# Schematic.net
KiCad netlist of a schematic drawn in EAGLE
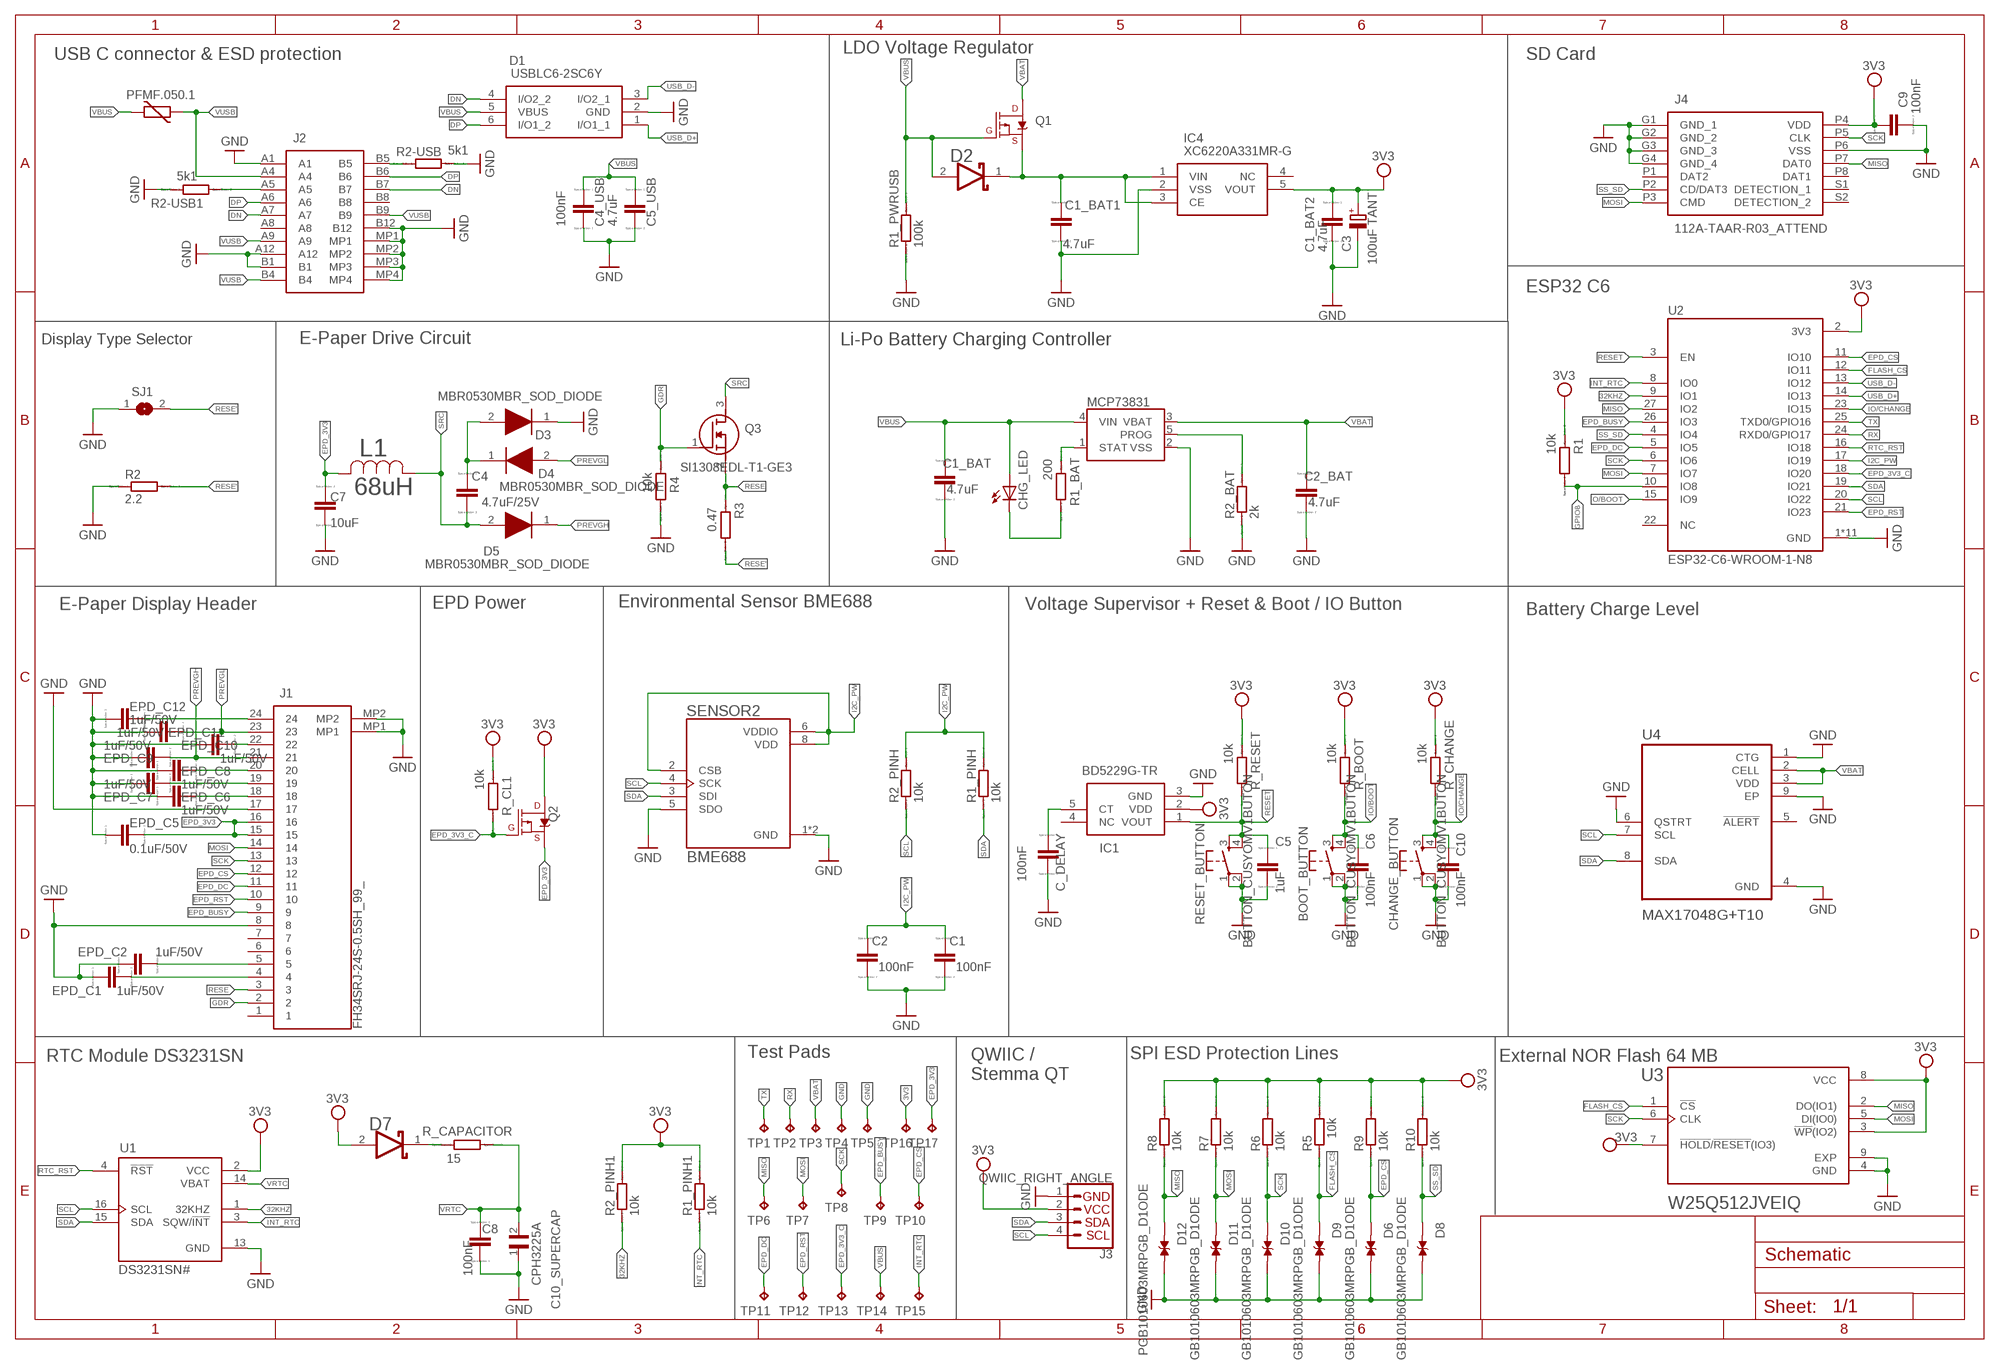
[diagram p0: schematic, sheet 1]

(export (version "E")
  (design (tool "Eeschema 10.0.6"))
  (components
    (comp (ref "BOOT_BUTTON")
      (value "BUTTON_CUSYOMV1BUTON")
      (footprint "eagle-import:MYBUTTON")
      (libsource (lib "eagle-import") (part "BUTTON_CUSYOMV1BUTON"))
    )
    (comp (ref "C1")
      (value "100nF")
      (footprint "eagle-import:ESP32_WROVER_EAGLE-LTSPICE_C0402")
      (libsource (lib "eagle-import") (part "ESP32_WROVER_EAGLE-LTSPICE_C"))
    )
    (comp (ref "C1_BAT")
      (value "4.7uF")
      (footprint "eagle-import:ESP32_WROVER_EAGLE-LTSPICE_C0402")
      (libsource (lib "eagle-import") (part "ESP32_WROVER_EAGLE-LTSPICE_C"))
    )
    (comp (ref "C1_BAT1")
      (value "4.7uF")
      (footprint "eagle-import:ESP32_WROVER_EAGLE-LTSPICE_C0402")
      (libsource (lib "eagle-import") (part "ESP32_WROVER_EAGLE-LTSPICE_C"))
    )
    (comp (ref "C1_BAT2")
      (value "4.7uF")
      (footprint "eagle-import:ESP32_WROVER_EAGLE-LTSPICE_C0402")
      (libsource (lib "eagle-import") (part "ESP32_WROVER_EAGLE-LTSPICE_C"))
    )
    (comp (ref "C2")
      (value "100nF")
      (footprint "eagle-import:ESP32_WROVER_EAGLE-LTSPICE_C0402")
      (libsource (lib "eagle-import") (part "ESP32_WROVER_EAGLE-LTSPICE_C"))
    )
    (comp (ref "C2_BAT")
      (value "4.7uF")
      (footprint "eagle-import:ESP32_WROVER_EAGLE-LTSPICE_C0402")
      (libsource (lib "eagle-import") (part "ESP32_WROVER_EAGLE-LTSPICE_C"))
    )
    (comp (ref "C3")
      (value "100uF TANT")
      (footprint "eagle-import:RCL_CT3528")
      (libsource (lib "eagle-import") (part "RCL_CPOL-EUCT3528"))
    )
    (comp (ref "C4")
      (value "4.7uF/25V")
      (footprint "eagle-import:ESP32_WROVER_EAGLE-LTSPICE_C0402")
      (libsource (lib "eagle-import") (part "ESP32_WROVER_EAGLE-LTSPICE_C"))
    )
    (comp (ref "C4_USB")
      (value "100nF")
      (footprint "eagle-import:ESP32_WROVER_EAGLE-LTSPICE_C0402")
      (libsource (lib "eagle-import") (part "ESP32_WROVER_EAGLE-LTSPICE_C"))
    )
    (comp (ref "C5")
      (value "1uF")
      (footprint "eagle-import:ESP32_WROVER_EAGLE-LTSPICE_C0402")
      (libsource (lib "eagle-import") (part "ESP32_WROVER_EAGLE-LTSPICE_C"))
    )
    (comp (ref "C5_USB")
      (value "4.7uF")
      (footprint "eagle-import:ESP32_WROVER_EAGLE-LTSPICE_C0402")
      (libsource (lib "eagle-import") (part "ESP32_WROVER_EAGLE-LTSPICE_C"))
    )
    (comp (ref "C6")
      (value "100nF")
      (footprint "eagle-import:ESP32_WROVER_EAGLE-LTSPICE_C0402")
      (libsource (lib "eagle-import") (part "ESP32_WROVER_EAGLE-LTSPICE_C"))
    )
    (comp (ref "C7")
      (value "10uF")
      (footprint "eagle-import:ESP32_WROVER_EAGLE-LTSPICE_C0402")
      (libsource (lib "eagle-import") (part "ESP32_WROVER_EAGLE-LTSPICE_C"))
    )
    (comp (ref "C8")
      (value "100nF")
      (footprint "eagle-import:ESP32_WROVER_EAGLE-LTSPICE_C0402")
      (libsource (lib "eagle-import") (part "ESP32_WROVER_EAGLE-LTSPICE_C"))
    )
    (comp (ref "C9")
      (value "100nF")
      (footprint "eagle-import:ESP32_WROVER_EAGLE-LTSPICE_C0402")
      (libsource (lib "eagle-import") (part "ESP32_WROVER_EAGLE-LTSPICE_C"))
    )
    (comp (ref "C10")
      (value "100nF")
      (footprint "eagle-import:ESP32_WROVER_EAGLE-LTSPICE_C0402")
      (libsource (lib "eagle-import") (part "ESP32_WROVER_EAGLE-LTSPICE_C"))
    )
    (comp (ref "C10_SUPERCAP")
      (value "CPH3225A")
      (footprint "eagle-import:CAPCP3225X100N")
      (fields (field (name "MF") "Seiko Instruments"))
      (libsource (lib "eagle-import") (part "CPH3225A"))
    )
    (comp (ref "CHANGE_BUTTON")
      (value "BUTTON_CUSYOMV1BUTON")
      (footprint "eagle-import:MYBUTTON")
      (libsource (lib "eagle-import") (part "BUTTON_CUSYOMV1BUTON"))
    )
    (comp (ref "CHG_LED")
      (value "ADAFRUIT_LEDCHIP-LED0603")
      (footprint "eagle-import:ADAFRUIT_CHIP-LED0603")
      (libsource (lib "eagle-import") (part "ADAFRUIT_LEDCHIP-LED0603"))
    )
    (comp (ref "C_DELAY")
      (value "100nF")
      (footprint "eagle-import:ESP32_WROVER_EAGLE-LTSPICE_C0402")
      (libsource (lib "eagle-import") (part "ESP32_WROVER_EAGLE-LTSPICE_C"))
    )
    (comp (ref "D1")
      (value "USBLC6-2SC6Y")
      (footprint "eagle-import:SOT95P280X145-6N")
      (fields (field (name "MF") "STMicroelectronics"))
      (libsource (lib "eagle-import") (part "USBLC6-2SC6Y"))
    )
    (comp (ref "D2")
      (value "ESP32_WROVER_AVX---SD0805S020S1R0_AVX_SD0805S020S1R0_0_0B1G_DIODE")
      (footprint "eagle-import:ESP32_WROVER_AVX---SD0805S020S1R0_AVX_SD0805S020S1R0_0")
      (libsource (lib "eagle-import") (part "ESP32_WROVER_AVX---SD0805S020S1R0_AVX_SD0805S020S1R0_0_0B1G_DIODE"))
    )
    (comp (ref "D3")
      (value "MBR0530MBR_SOD_DIODE")
      (footprint "eagle-import:SOD3716X135N")
      (libsource (lib "eagle-import") (part "MBR0530MBR_SOD_DIODE"))
    )
    (comp (ref "D4")
      (value "MBR0530MBR_SOD_DIODE")
      (footprint "eagle-import:SOD3716X135N")
      (libsource (lib "eagle-import") (part "MBR0530MBR_SOD_DIODE"))
    )
    (comp (ref "D5")
      (value "MBR0530MBR_SOD_DIODE")
      (footprint "eagle-import:SOD3716X135N")
      (libsource (lib "eagle-import") (part "MBR0530MBR_SOD_DIODE"))
    )
    (comp (ref "D6")
      (value "PGB1010603MRPGB_D1ODE")
      (footprint "eagle-import:DIOC1608X36N")
      (libsource (lib "eagle-import") (part "PGB1010603MRPGB_D1ODE"))
    )
    (comp (ref "D7")
      (value "ESP32_WROVER_AVX---SD0805S020S1R0_AVX_SD0805S020S1R0_0_0B1G_DIODE")
      (footprint "eagle-import:ESP32_WROVER_AVX---SD0805S020S1R0_AVX_SD0805S020S1R0_0")
      (libsource (lib "eagle-import") (part "ESP32_WROVER_AVX---SD0805S020S1R0_AVX_SD0805S020S1R0_0_0B1G_DIODE"))
    )
    (comp (ref "D8")
      (value "PGB1010603MRPGB_D1ODE")
      (footprint "eagle-import:DIOC1608X36N")
      (libsource (lib "eagle-import") (part "PGB1010603MRPGB_D1ODE"))
    )
    (comp (ref "D9")
      (value "PGB1010603MRPGB_D1ODE")
      (footprint "eagle-import:DIOC1608X36N")
      (libsource (lib "eagle-import") (part "PGB1010603MRPGB_D1ODE"))
    )
    (comp (ref "D10")
      (value "PGB1010603MRPGB_D1ODE")
      (footprint "eagle-import:DIOC1608X36N")
      (libsource (lib "eagle-import") (part "PGB1010603MRPGB_D1ODE"))
    )
    (comp (ref "D11")
      (value "PGB1010603MRPGB_D1ODE")
      (footprint "eagle-import:DIOC1608X36N")
      (libsource (lib "eagle-import") (part "PGB1010603MRPGB_D1ODE"))
    )
    (comp (ref "D12")
      (value "PGB1010603MRPGB_D1ODE")
      (footprint "eagle-import:DIOC1608X36N")
      (libsource (lib "eagle-import") (part "PGB1010603MRPGB_D1ODE"))
    )
    (comp (ref "EPD_C1")
      (value "1uF/50V")
      (footprint "eagle-import:ESP32_WROVER_EAGLE-LTSPICE_C0402")
      (libsource (lib "eagle-import") (part "ESP32_WROVER_EAGLE-LTSPICE_C"))
    )
    (comp (ref "EPD_C2")
      (value "1uF/50V")
      (footprint "eagle-import:ESP32_WROVER_EAGLE-LTSPICE_C0402")
      (libsource (lib "eagle-import") (part "ESP32_WROVER_EAGLE-LTSPICE_C"))
    )
    (comp (ref "EPD_C5")
      (value "0.1uF/50V")
      (footprint "eagle-import:ESP32_WROVER_EAGLE-LTSPICE_C0402")
      (libsource (lib "eagle-import") (part "ESP32_WROVER_EAGLE-LTSPICE_C"))
    )
    (comp (ref "EPD_C6")
      (value "1uF/50V")
      (footprint "eagle-import:ESP32_WROVER_EAGLE-LTSPICE_C0402")
      (libsource (lib "eagle-import") (part "ESP32_WROVER_EAGLE-LTSPICE_C"))
    )
    (comp (ref "EPD_C7")
      (value "1uF/50V")
      (footprint "eagle-import:ESP32_WROVER_EAGLE-LTSPICE_C0402")
      (libsource (lib "eagle-import") (part "ESP32_WROVER_EAGLE-LTSPICE_C"))
    )
    (comp (ref "EPD_C8")
      (value "1uF/50V")
      (footprint "eagle-import:ESP32_WROVER_EAGLE-LTSPICE_C0402")
      (libsource (lib "eagle-import") (part "ESP32_WROVER_EAGLE-LTSPICE_C"))
    )
    (comp (ref "EPD_C9")
      (value "1uF/50V")
      (footprint "eagle-import:ESP32_WROVER_EAGLE-LTSPICE_C0402")
      (libsource (lib "eagle-import") (part "ESP32_WROVER_EAGLE-LTSPICE_C"))
    )
    (comp (ref "EPD_C10")
      (value "1uF/50V")
      (footprint "eagle-import:ESP32_WROVER_EAGLE-LTSPICE_C0402")
      (libsource (lib "eagle-import") (part "ESP32_WROVER_EAGLE-LTSPICE_C"))
    )
    (comp (ref "EPD_C11")
      (value "1uF/50V")
      (footprint "eagle-import:ESP32_WROVER_EAGLE-LTSPICE_C0402")
      (libsource (lib "eagle-import") (part "ESP32_WROVER_EAGLE-LTSPICE_C"))
    )
    (comp (ref "EPD_C12")
      (value "1uF/50V")
      (footprint "eagle-import:ESP32_WROVER_EAGLE-LTSPICE_C0402")
      (libsource (lib "eagle-import") (part "ESP32_WROVER_EAGLE-LTSPICE_C"))
    )
    (comp (ref "IC1")
      (value "BD5229G-TR")
      (footprint "eagle-import:SOT95P280X125-5N")
      (fields (field (name "MOUSER_PART_NUMBER") "755-BD5229G-TR"))
      (libsource (lib "eagle-import") (part "BD5229G-TR"))
    )
    (comp (ref "IC4")
      (value "XC6220A331MR-G")
      (footprint "eagle-import:SOT95P280X120-5N")
      (fields (field (name "MOUSER_PART_NUMBER") "865-XC6220A331MR-G"))
      (libsource (lib "eagle-import") (part "XC6220A331MR-G"))
    )
    (comp (ref "J1")
      (value "FH34SRJ-24S-0.5SH_99_")
      (footprint "eagle-import:FH34SRJ24S05SH99")
      (fields
        (field (name "MANUFACTURER_PART_NUMBER") "FH34SRJ-24S-0.5SH(99)")
        (field (name "MOUSER_PART_NUMBER") "798-FH34SRJ24S05SH99")
      )
      (libsource (lib "eagle-import") (part "FH34SRJ-24S-0.5SH_99_"))
    )
    (comp (ref "J2")
      (value "SAMACSYS_PARTS_USB4110-GF-A")
      (footprint "eagle-import:SAMACSYS_PARTS_USB4110GFA")
      (fields
        (field (name "MANUFACTURER_PART_NUMBER") "USB4110-GF-A")
        (field (name "MOUSER_PART_NUMBER") "640-USB4110-GF-A")
      )
      (libsource (lib "eagle-import") (part "SAMACSYS_PARTS_USB4110-GF-A"))
    )
    (comp (ref "J3")
      (value "QWIIC_RIGHT_ANGLE")
      (footprint "eagle-import:JST04_1MM_RA")
      (libsource (lib "eagle-import") (part "QWIIC_CONNECTORJS-1MM"))
    )
    (comp (ref "J4")
      (value "112A-TAAR-R03_ATTEND")
      (footprint "eagle-import:112ATAARR03ATTEND")
      (fields (field (name "MANUFACTURER_PART_NUMBER") "112A-TAAR-R03 ATTEND"))
      (libsource (lib "eagle-import") (part "112A-TAAR-R03_ATTEND"))
    )
    (comp (ref "L1")
      (value "68uH")
      (footprint "eagle-import:IND_4828-WE-TPC_WRE")
      (fields
        (field (name "MANUFACTURER_PART_NUMBER") "744043680")
        (field (name "COPYRIGHT") "Copyright (C) 2024 Ultra Librarian. All rights reserved.")
      )
      (libsource (lib "eagle-import") (part "744043680IND_4828-WE-TPC_WRE"))
    )
    (comp (ref "MCP73831")
      (value "ESP32_WROVER_SPARKFUN-IC-POWER_MCP73831")
      (footprint "eagle-import:ESP32_WROVER_SPARKFUN-IC-POWER_SOT23-5")
      (libsource (lib "eagle-import") (part "ESP32_WROVER_SPARKFUN-IC-POWER_MCP73831"))
    )
    (comp (ref "PFMF.050.1")
      (value "ESP32C6_VARISTORPFMF_ESP32C6_VARISTORS")
      (footprint "eagle-import:ESP32C6_VARISTOR_CT_CN1812")
      (libsource (lib "eagle-import") (part "ESP32C6_VARISTORPFMF_ESP32C6_VARISTORS"))
    )
    (comp (ref "Q1")
      (value "20V/4.2A/52mΩ/1.4W")
      (footprint "eagle-import:ESP32_WROVER_SPARKFUN-DISCRETESEMI_SOT23-3")
      (libsource (lib "eagle-import") (part "ESP32_WROVER_SPARKFUN-DISCRETESEMI_MOSFET_PCH"))
    )
    (comp (ref "Q2")
      (value "20V/4.2A/52mΩ/1.4W")
      (footprint "eagle-import:ESP32_WROVER_SPARKFUN-DISCRETESEMI_SOT23-3")
      (libsource (lib "eagle-import") (part "ESP32_WROVER_SPARKFUN-DISCRETESEMI_MOSFET_PCH"))
    )
    (comp (ref "Q3")
      (value "SI1308EDL-T1-GE3")
      (footprint "eagle-import:SOT65P210X110-3N")
      (fields (field (name "MF") "Vishay Siliconix"))
      (libsource (lib "eagle-import") (part "SI1308EDL-T1-GE3"))
    )
    (comp (ref "R1")
      (value "10k")
      (footprint "eagle-import:ESP32_WROVER_EAGLE-LTSPICE_R0402")
      (libsource (lib "eagle-import") (part "ESP32_WROVER_EAGLE-LTSPICE_R"))
    )
    (comp (ref "R1_BAT")
      (value "200")
      (footprint "eagle-import:ESP32_WROVER_EAGLE-LTSPICE_R0402")
      (libsource (lib "eagle-import") (part "ESP32_WROVER_EAGLE-LTSPICE_R"))
    )
    (comp (ref "R1_PINH")
      (value "10k")
      (footprint "eagle-import:ESP32_WROVER_EAGLE-LTSPICE_R0402")
      (libsource (lib "eagle-import") (part "ESP32_WROVER_EAGLE-LTSPICE_R"))
    )
    (comp (ref "R1_PINH1")
      (value "10k")
      (footprint "eagle-import:ESP32_WROVER_EAGLE-LTSPICE_R0402")
      (libsource (lib "eagle-import") (part "ESP32_WROVER_EAGLE-LTSPICE_R"))
    )
    (comp (ref "R1_PWRUSB")
      (value "100k")
      (footprint "eagle-import:ESP32_WROVER_EAGLE-LTSPICE_R0402")
      (libsource (lib "eagle-import") (part "ESP32_WROVER_EAGLE-LTSPICE_R"))
    )
    (comp (ref "R2")
      (value "2.2")
      (footprint "eagle-import:ESP32_WROVER_EAGLE-LTSPICE_R0402")
      (libsource (lib "eagle-import") (part "ESP32_WROVER_EAGLE-LTSPICE_R"))
    )
    (comp (ref "R2-USB")
      (value "5k1")
      (footprint "eagle-import:ESP32_WROVER_EAGLE-LTSPICE_R0402")
      (libsource (lib "eagle-import") (part "ESP32_WROVER_EAGLE-LTSPICE_R"))
    )
    (comp (ref "R2-USB1")
      (value "5k1")
      (footprint "eagle-import:ESP32_WROVER_EAGLE-LTSPICE_R0402")
      (libsource (lib "eagle-import") (part "ESP32_WROVER_EAGLE-LTSPICE_R"))
    )
    (comp (ref "R2_BAT")
      (value "2k")
      (footprint "eagle-import:ESP32_WROVER_EAGLE-LTSPICE_R0402")
      (libsource (lib "eagle-import") (part "ESP32_WROVER_EAGLE-LTSPICE_R"))
    )
    (comp (ref "R2_PINH")
      (value "10k")
      (footprint "eagle-import:ESP32_WROVER_EAGLE-LTSPICE_R0402")
      (libsource (lib "eagle-import") (part "ESP32_WROVER_EAGLE-LTSPICE_R"))
    )
    (comp (ref "R2_PINH1")
      (value "10k")
      (footprint "eagle-import:ESP32_WROVER_EAGLE-LTSPICE_R0402")
      (libsource (lib "eagle-import") (part "ESP32_WROVER_EAGLE-LTSPICE_R"))
    )
    (comp (ref "R3")
      (value "0.47")
      (footprint "eagle-import:ESP32_WROVER_EAGLE-LTSPICE_R0402")
      (libsource (lib "eagle-import") (part "ESP32_WROVER_EAGLE-LTSPICE_R"))
    )
    (comp (ref "R4")
      (value "10k")
      (footprint "eagle-import:ESP32_WROVER_EAGLE-LTSPICE_R0402")
      (libsource (lib "eagle-import") (part "ESP32_WROVER_EAGLE-LTSPICE_R"))
    )
    (comp (ref "R5")
      (value "10k")
      (footprint "eagle-import:ESP32_WROVER_EAGLE-LTSPICE_R0402")
      (libsource (lib "eagle-import") (part "ESP32_WROVER_EAGLE-LTSPICE_R"))
    )
    (comp (ref "R6")
      (value "10k")
      (footprint "eagle-import:ESP32_WROVER_EAGLE-LTSPICE_R0402")
      (libsource (lib "eagle-import") (part "ESP32_WROVER_EAGLE-LTSPICE_R"))
    )
    (comp (ref "R7")
      (value "10k")
      (footprint "eagle-import:ESP32_WROVER_EAGLE-LTSPICE_R0402")
      (libsource (lib "eagle-import") (part "ESP32_WROVER_EAGLE-LTSPICE_R"))
    )
    (comp (ref "R8")
      (value "10k")
      (footprint "eagle-import:ESP32_WROVER_EAGLE-LTSPICE_R0402")
      (libsource (lib "eagle-import") (part "ESP32_WROVER_EAGLE-LTSPICE_R"))
    )
    (comp (ref "R9")
      (value "10k")
      (footprint "eagle-import:ESP32_WROVER_EAGLE-LTSPICE_R0402")
      (libsource (lib "eagle-import") (part "ESP32_WROVER_EAGLE-LTSPICE_R"))
    )
    (comp (ref "R10")
      (value "10k")
      (footprint "eagle-import:ESP32_WROVER_EAGLE-LTSPICE_R0402")
      (libsource (lib "eagle-import") (part "ESP32_WROVER_EAGLE-LTSPICE_R"))
    )
    (comp (ref "RESET_BUTTON")
      (value "BUTTON_CUSYOMV1BUTON")
      (footprint "eagle-import:MYBUTTON")
      (libsource (lib "eagle-import") (part "BUTTON_CUSYOMV1BUTON"))
    )
    (comp (ref "R_BOOT")
      (value "10k")
      (footprint "eagle-import:ESP32_WROVER_EAGLE-LTSPICE_R0402")
      (libsource (lib "eagle-import") (part "ESP32_WROVER_EAGLE-LTSPICE_R"))
    )
    (comp (ref "R_CAPACITOR")
      (value "15")
      (footprint "eagle-import:ESP32_WROVER_EAGLE-LTSPICE_R0402")
      (libsource (lib "eagle-import") (part "ESP32_WROVER_EAGLE-LTSPICE_R"))
    )
    (comp (ref "R_CHANGE")
      (value "10k")
      (footprint "eagle-import:ESP32_WROVER_EAGLE-LTSPICE_R0402")
      (libsource (lib "eagle-import") (part "ESP32_WROVER_EAGLE-LTSPICE_R"))
    )
    (comp (ref "R_CL1")
      (value "10k")
      (footprint "eagle-import:ESP32_WROVER_EAGLE-LTSPICE_R0402")
      (libsource (lib "eagle-import") (part "ESP32_WROVER_EAGLE-LTSPICE_R"))
    )
    (comp (ref "R_RESET")
      (value "10k")
      (footprint "eagle-import:ESP32_WROVER_EAGLE-LTSPICE_R0402")
      (libsource (lib "eagle-import") (part "ESP32_WROVER_EAGLE-LTSPICE_R"))
    )
    (comp (ref "SENSOR2")
      (value "BME688")
      (footprint "eagle-import:ESP32_WROVER_BME680_PSON80P300X300X100-8N")
      (fields (field (name "MF") "Bosch Sensortec") (field (name "MP") "BME680"))
      (libsource (lib "eagle-import") (part "ESP32_WROVER_BME680_BME680"))
    )
    (comp (ref "SJ1") (value "SJ") (footprint "eagle-import:SJ") (libsource (lib "eagle-import") (part "SJ")))
    (comp (ref "TP1")
      (value "TPTP20R")
      (footprint "eagle-import:TP20R")
      (libsource (lib "eagle-import") (part "TPTP20R"))
    )
    (comp (ref "TP2")
      (value "TPTP20R")
      (footprint "eagle-import:TP20R")
      (libsource (lib "eagle-import") (part "TPTP20R"))
    )
    (comp (ref "TP3")
      (value "TPTP20R")
      (footprint "eagle-import:TP20R")
      (libsource (lib "eagle-import") (part "TPTP20R"))
    )
    (comp (ref "TP4")
      (value "TPTP20R")
      (footprint "eagle-import:TP20R")
      (libsource (lib "eagle-import") (part "TPTP20R"))
    )
    (comp (ref "TP5")
      (value "TPTP20R")
      (footprint "eagle-import:TP20R")
      (libsource (lib "eagle-import") (part "TPTP20R"))
    )
    (comp (ref "TP6")
      (value "TPTP20R")
      (footprint "eagle-import:TP20R")
      (libsource (lib "eagle-import") (part "TPTP20R"))
    )
    (comp (ref "TP7")
      (value "TPTP20R")
      (footprint "eagle-import:TP20R")
      (libsource (lib "eagle-import") (part "TPTP20R"))
    )
    (comp (ref "TP8")
      (value "TPTP20R")
      (footprint "eagle-import:TP20R")
      (libsource (lib "eagle-import") (part "TPTP20R"))
    )
    (comp (ref "TP9")
      (value "TPTP20R")
      (footprint "eagle-import:TP20R")
      (libsource (lib "eagle-import") (part "TPTP20R"))
    )
    (comp (ref "TP10")
      (value "TPTP20R")
      (footprint "eagle-import:TP20R")
      (libsource (lib "eagle-import") (part "TPTP20R"))
    )
    (comp (ref "TP11")
      (value "TPTP20R")
      (footprint "eagle-import:TP20R")
      (libsource (lib "eagle-import") (part "TPTP20R"))
    )
    (comp (ref "TP12")
      (value "TPTP20R")
      (footprint "eagle-import:TP20R")
      (libsource (lib "eagle-import") (part "TPTP20R"))
    )
    (comp (ref "TP13")
      (value "TPTP20R")
      (footprint "eagle-import:TP20R")
      (libsource (lib "eagle-import") (part "TPTP20R"))
    )
    (comp (ref "TP14")
      (value "TPTP20R")
      (footprint "eagle-import:TP20R")
      (libsource (lib "eagle-import") (part "TPTP20R"))
    )
    (comp (ref "TP15")
      (value "TPTP20R")
      (footprint "eagle-import:TP20R")
      (libsource (lib "eagle-import") (part "TPTP20R"))
    )
    (comp (ref "TP16")
      (value "TPTP20R")
      (footprint "eagle-import:TP20R")
      (libsource (lib "eagle-import") (part "TPTP20R"))
    )
    (comp (ref "TP17")
      (value "TPTP20R")
      (footprint "eagle-import:TP20R")
      (libsource (lib "eagle-import") (part "TPTP20R"))
    )
    (comp (ref "U1")
      (value "DS3231SN#")
      (footprint "eagle-import:SOIC127P1032X265-16N")
      (fields (field (name "MF") "Analog Devices"))
      (libsource (lib "eagle-import") (part "DS3231SN#"))
    )
    (comp (ref "U2")
      (value "ESP32-C6-WROOM-1-N8")
      (footprint "eagle-import:XCVR_ESP32-C6-WROOM-1-N8")
      (fields (field (name "MF") "Espressif Systems"))
      (libsource (lib "eagle-import") (part "ESP32-C6-WROOM-1-N8"))
    )
    (comp (ref "U3")
      (value "W25Q512JVEIQ")
      (footprint "eagle-import:SON127P600X800X80-9N")
      (fields (field (name "MF") "Winbond Electronics"))
      (libsource (lib "eagle-import") (part "W25Q512JVEIQ"))
    )
    (comp (ref "U4")
      (value "MAX17048G+T10")
      (footprint "eagle-import:SON50P200X200X80-9N")
      (fields (field (name "MF") "Analog Devices"))
      (libsource (lib "eagle-import") (part "MAX17048G+T10"))
    )
  )
  (nets
    (net (code "1") (name "3V3") (class "Default")
      (node (ref "C1_BAT2") (pin "1") (pinfunction "1_1") (pintype "passive"))
      (node (ref "C3") (pin "+") (pinfunction "+_+") (pintype "passive"))
      (node (ref "C9") (pin "1") (pinfunction "1_1") (pintype "passive"))
      (node (ref "D7") (pin "2") (pinfunction "ANODE_2") (pintype "bidirectional"))
      (node (ref "IC1") (pin "2") (pinfunction "VDD_2") (pintype "bidirectional"))
      (node (ref "IC4") (pin "5") (pinfunction "VOUT_5") (pintype "bidirectional"))
      (node (ref "J3") (pin "2") (pinfunction "2_2") (pintype "power_in"))
      (node (ref "J4") (pin "P4") (pinfunction "VDD_P4") (pintype "bidirectional"))
      (node (ref "Q2") (pin "3") (pinfunction "D_3") (pintype "bidirectional"))
      (node (ref "R1") (pin "2") (pinfunction "2_2") (pintype "passive"))
      (node (ref "R10") (pin "2") (pinfunction "2_2") (pintype "passive"))
      (node (ref "R1_PINH1") (pin "2") (pinfunction "2_2") (pintype "passive"))
      (node (ref "R2_PINH1") (pin "2") (pinfunction "2_2") (pintype "passive"))
      (node (ref "R5") (pin "2") (pinfunction "2_2") (pintype "passive"))
      (node (ref "R6") (pin "2") (pinfunction "2_2") (pintype "passive"))
      (node (ref "R7") (pin "2") (pinfunction "2_2") (pintype "passive"))
      (node (ref "R8") (pin "2") (pinfunction "2_2") (pintype "passive"))
      (node (ref "R9") (pin "2") (pinfunction "2_2") (pintype "passive"))
      (node (ref "R_BOOT") (pin "2") (pinfunction "2_2") (pintype "passive"))
      (node (ref "R_CHANGE") (pin "2") (pinfunction "2_2") (pintype "passive"))
      (node (ref "R_CL1") (pin "2") (pinfunction "2_2") (pintype "passive"))
      (node (ref "R_RESET") (pin "2") (pinfunction "2_2") (pintype "passive"))
      (node (ref "TP16") (pin "TP") (pinfunction "TP_TP") (pintype "input"))
      (node (ref "U1") (pin "2") (pinfunction "VCC_2") (pintype "power_in"))
      (node (ref "U2") (pin "2") (pinfunction "3V3_2") (pintype "power_in"))
      (node (ref "U3") (pin "3") (pinfunction "~{WP}(IO2)_3") (pintype "bidirectional"))
      (node (ref "U3") (pin "7") (pinfunction "~{HOLD}/~{RESET}(IO3)_7") (pintype "bidirectional"))
      (node (ref "U3") (pin "8") (pinfunction "VCC_8") (pintype "power_in"))
    )
    (net (code "2") (name "32KHZ") (class "Default")
      (node (ref "R2_PINH1") (pin "1") (pinfunction "1_1") (pintype "passive"))
      (node (ref "U1") (pin "1") (pinfunction "32KHZ_1") (pintype "output"))
      (node (ref "U2") (pin "9") (pinfunction "IO1_9") (pintype "bidirectional"))
    )
    (net (code "3") (name "DN") (class "Default")
      (node (ref "D1") (pin "4") (pinfunction "I/O2_2_4") (pintype "bidirectional"))
      (node (ref "J2") (pin "A7") (pinfunction "A7_A7") (pintype "bidirectional"))
      (node (ref "J2") (pin "B7") (pinfunction "B7_B7") (pintype "bidirectional"))
    )
    (net (code "4") (name "DP") (class "Default")
      (node (ref "D1") (pin "6") (pinfunction "I/O1_2_6") (pintype "bidirectional"))
      (node (ref "J2") (pin "A6") (pinfunction "A6_A6") (pintype "bidirectional"))
      (node (ref "J2") (pin "B6") (pinfunction "B6_B6") (pintype "bidirectional"))
    )
    (net (code "5") (name "EPD_3V3") (class "Default")
      (node (ref "C7") (pin "2") (pinfunction "2_2") (pintype "passive"))
      (node (ref "EPD_C5") (pin "2") (pinfunction "2_2") (pintype "passive"))
      (node (ref "J1") (pin "15") (pinfunction "15_15") (pintype "bidirectional"))
      (node (ref "J1") (pin "16") (pinfunction "16_16") (pintype "bidirectional"))
      (node (ref "L1") (pin "2") (pinfunction "2_2") (pintype "passive"))
      (node (ref "Q2") (pin "2") (pinfunction "S_2") (pintype "bidirectional"))
      (node (ref "TP17") (pin "TP") (pinfunction "TP_TP") (pintype "input"))
    )
    (net (code "6") (name "EPD_3V3_C") (class "Default")
      (node (ref "Q2") (pin "1") (pinfunction "G_1") (pintype "bidirectional"))
      (node (ref "R_CL1") (pin "1") (pinfunction "1_1") (pintype "passive"))
      (node (ref "TP13") (pin "TP") (pinfunction "TP_TP") (pintype "input"))
      (node (ref "U2") (pin "18") (pinfunction "IO20_18") (pintype "bidirectional"))
    )
    (net (code "7") (name "EPD_BUSY") (class "Default")
      (node (ref "J1") (pin "9") (pinfunction "9_9") (pintype "bidirectional"))
      (node (ref "TP9") (pin "TP") (pinfunction "TP_TP") (pintype "input"))
      (node (ref "U2") (pin "26") (pinfunction "IO3_26") (pintype "bidirectional"))
    )
    (net (code "8") (name "EPD_CS") (class "Default")
      (node (ref "D6") (pin "1") (pinfunction "1_1") (pintype "passive"))
      (node (ref "J1") (pin "12") (pinfunction "12_12") (pintype "bidirectional"))
      (node (ref "R9") (pin "1") (pinfunction "1_1") (pintype "passive"))
      (node (ref "TP10") (pin "TP") (pinfunction "TP_TP") (pintype "input"))
      (node (ref "U2") (pin "11") (pinfunction "IO10_11") (pintype "bidirectional"))
    )
    (net (code "9") (name "EPD_DC") (class "Default")
      (node (ref "J1") (pin "11") (pinfunction "11_11") (pintype "bidirectional"))
      (node (ref "TP11") (pin "TP") (pinfunction "TP_TP") (pintype "input"))
      (node (ref "U2") (pin "5") (pinfunction "IO5_5") (pintype "bidirectional"))
    )
    (net (code "10") (name "EPD_RST") (class "Default")
      (node (ref "J1") (pin "10") (pinfunction "10_10") (pintype "bidirectional"))
      (node (ref "TP12") (pin "TP") (pinfunction "TP_TP") (pintype "input"))
      (node (ref "U2") (pin "21") (pinfunction "IO23_21") (pintype "bidirectional"))
    )
    (net (code "11") (name "FLASH_CS") (class "Default")
      (node (ref "D9") (pin "1") (pinfunction "1_1") (pintype "passive"))
      (node (ref "R5") (pin "1") (pinfunction "1_1") (pintype "passive"))
      (node (ref "U2") (pin "12") (pinfunction "IO11_12") (pintype "bidirectional"))
      (node (ref "U3") (pin "1") (pinfunction "~{CS}_1") (pintype "input"))
    )
    (net (code "12") (name "GDR") (class "Default")
      (node (ref "J1") (pin "2") (pinfunction "2_2") (pintype "bidirectional"))
      (node (ref "Q3") (pin "1") (pinfunction "G_1") (pintype "bidirectional"))
      (node (ref "R4") (pin "2") (pinfunction "2_2") (pintype "passive"))
    )
    (net (code "13") (name "GND") (class "Default")
      (node (ref "BOOT_BUTTON") (pin "1") (pinfunction "1_1") (pintype "passive"))
      (node (ref "BOOT_BUTTON") (pin "2") (pinfunction "2_2") (pintype "passive"))
      (node (ref "C1") (pin "2") (pinfunction "2_2") (pintype "passive"))
      (node (ref "C10") (pin "2") (pinfunction "2_2") (pintype "passive"))
      (node (ref "C10_SUPERCAP") (pin "1") (pinfunction "1_1") (pintype "passive"))
      (node (ref "C1_BAT") (pin "2") (pinfunction "2_2") (pintype "passive"))
      (node (ref "C1_BAT1") (pin "2") (pinfunction "2_2") (pintype "passive"))
      (node (ref "C1_BAT2") (pin "2") (pinfunction "2_2") (pintype "passive"))
      (node (ref "C2") (pin "2") (pinfunction "2_2") (pintype "passive"))
      (node (ref "C2_BAT") (pin "2") (pinfunction "2_2") (pintype "passive"))
      (node (ref "C3") (pin "-") (pinfunction "-_-") (pintype "passive"))
      (node (ref "C4_USB") (pin "2") (pinfunction "2_2") (pintype "passive"))
      (node (ref "C5") (pin "2") (pinfunction "2_2") (pintype "passive"))
      (node (ref "C5_USB") (pin "2") (pinfunction "2_2") (pintype "passive"))
      (node (ref "C6") (pin "2") (pinfunction "2_2") (pintype "passive"))
      (node (ref "C7") (pin "1") (pinfunction "1_1") (pintype "passive"))
      (node (ref "C8") (pin "1") (pinfunction "1_1") (pintype "passive"))
      (node (ref "C9") (pin "2") (pinfunction "2_2") (pintype "passive"))
      (node (ref "CHANGE_BUTTON") (pin "1") (pinfunction "1_1") (pintype "passive"))
      (node (ref "CHANGE_BUTTON") (pin "2") (pinfunction "2_2") (pintype "passive"))
      (node (ref "C_DELAY") (pin "2") (pinfunction "2_2") (pintype "passive"))
      (node (ref "D1") (pin "2") (pinfunction "GND_2") (pintype "bidirectional"))
      (node (ref "D10") (pin "2") (pinfunction "2_2") (pintype "passive"))
      (node (ref "D11") (pin "2") (pinfunction "2_2") (pintype "passive"))
      (node (ref "D12") (pin "2") (pinfunction "2_2") (pintype "passive"))
      (node (ref "D3") (pin "1") (pinfunction "K_1") (pintype "bidirectional"))
      (node (ref "D6") (pin "2") (pinfunction "2_2") (pintype "passive"))
      (node (ref "D8") (pin "2") (pinfunction "2_2") (pintype "passive"))
      (node (ref "D9") (pin "2") (pinfunction "2_2") (pintype "passive"))
      (node (ref "EPD_C1") (pin "1") (pinfunction "1_1") (pintype "passive"))
      (node (ref "EPD_C10") (pin "1") (pinfunction "1_1") (pintype "passive"))
      (node (ref "EPD_C11") (pin "1") (pinfunction "1_1") (pintype "passive"))
      (node (ref "EPD_C12") (pin "1") (pinfunction "1_1") (pintype "passive"))
      (node (ref "EPD_C2") (pin "1") (pinfunction "1_1") (pintype "passive"))
      (node (ref "EPD_C5") (pin "1") (pinfunction "1_1") (pintype "passive"))
      (node (ref "EPD_C6") (pin "1") (pinfunction "1_1") (pintype "passive"))
      (node (ref "EPD_C7") (pin "1") (pinfunction "1_1") (pintype "passive"))
      (node (ref "EPD_C8") (pin "1") (pinfunction "1_1") (pintype "passive"))
      (node (ref "EPD_C9") (pin "1") (pinfunction "1_1") (pintype "passive"))
      (node (ref "IC1") (pin "3") (pinfunction "GND_3") (pintype "bidirectional"))
      (node (ref "IC4") (pin "2") (pinfunction "VSS_2") (pintype "bidirectional"))
      (node (ref "J1") (pin "17") (pinfunction "17_17") (pintype "bidirectional"))
      (node (ref "J1") (pin "8") (pinfunction "8_8") (pintype "bidirectional"))
      (node (ref "J1") (pin "MP1") (pinfunction "MP1_MP1") (pintype "bidirectional"))
      (node (ref "J1") (pin "MP2") (pinfunction "MP2_MP2") (pintype "bidirectional"))
      (node (ref "J2") (pin "A1") (pinfunction "A1_A1") (pintype "bidirectional"))
      (node (ref "J2") (pin "A12") (pinfunction "A12_A12") (pintype "bidirectional"))
      (node (ref "J2") (pin "B1") (pinfunction "B1_B1") (pintype "bidirectional"))
      (node (ref "J2") (pin "B12") (pinfunction "B12_B12") (pintype "bidirectional"))
      (node (ref "J2") (pin "MP1") (pinfunction "MP1_MP1") (pintype "bidirectional"))
      (node (ref "J2") (pin "MP2") (pinfunction "MP2_MP2") (pintype "bidirectional"))
      (node (ref "J2") (pin "MP3") (pinfunction "MP3_MP3") (pintype "bidirectional"))
      (node (ref "J2") (pin "MP4") (pinfunction "MP4_MP4") (pintype "bidirectional"))
      (node (ref "J3") (pin "1") (pinfunction "1_1") (pintype "power_in"))
      (node (ref "J4") (pin "G1") (pinfunction "GND_1_G1") (pintype "bidirectional"))
      (node (ref "J4") (pin "G2") (pinfunction "GND_2_G2") (pintype "bidirectional"))
      (node (ref "J4") (pin "G3") (pinfunction "GND_3_G3") (pintype "bidirectional"))
      (node (ref "J4") (pin "G4") (pinfunction "GND_4_G4") (pintype "bidirectional"))
      (node (ref "J4") (pin "P6") (pinfunction "VSS_P6") (pintype "bidirectional"))
      (node (ref "MCP73831") (pin "2") (pinfunction "VSS_2") (pintype "power_in"))
      (node (ref "R1_PWRUSB") (pin "1") (pinfunction "1_1") (pintype "passive"))
      (node (ref "R2") (pin "1") (pinfunction "1_1") (pintype "passive"))
      (node (ref "R2-USB") (pin "2") (pinfunction "2_2") (pintype "passive"))
      (node (ref "R2-USB1") (pin "1") (pinfunction "1_1") (pintype "passive"))
      (node (ref "R2_BAT") (pin "1") (pinfunction "1_1") (pintype "passive"))
      (node (ref "R4") (pin "1") (pinfunction "1_1") (pintype "passive"))
      (node (ref "RESET_BUTTON") (pin "1") (pinfunction "1_1") (pintype "passive"))
      (node (ref "RESET_BUTTON") (pin "2") (pinfunction "2_2") (pintype "passive"))
      (node (ref "SENSOR2") (pin "1") (pinfunction "GND_1") (pintype "power_in"))
      (node (ref "SENSOR2") (pin "5") (pinfunction "SDO_5") (pintype "bidirectional"))
      (node (ref "SENSOR2") (pin "7") (pinfunction "GND_7") (pintype "power_in"))
      (node (ref "SJ1") (pin "1") (pinfunction "1_1") (pintype "passive"))
      (node (ref "TP4") (pin "TP") (pinfunction "TP_TP") (pintype "input"))
      (node (ref "TP5") (pin "TP") (pinfunction "TP_TP") (pintype "input"))
      (node (ref "U1") (pin "13") (pinfunction "GND_13") (pintype "power_in"))
      (node (ref "U2") (pin "1") (pinfunction "GND_1") (pintype "power_in"))
      (node (ref "U2") (pin "28") (pinfunction "GND_28") (pintype "power_in"))
      (node (ref "U2") (pin "29_1") (pinfunction "GND_29_1") (pintype "power_in"))
      (node (ref "U2") (pin "29_2") (pinfunction "GND_29_2") (pintype "power_in"))
      (node (ref "U2") (pin "29_3") (pinfunction "GND_29_3") (pintype "power_in"))
      (node (ref "U2") (pin "29_4") (pinfunction "GND_29_4") (pintype "power_in"))
      (node (ref "U2") (pin "29_5") (pinfunction "GND_29_5") (pintype "power_in"))
      (node (ref "U2") (pin "29_6") (pinfunction "GND_29_6") (pintype "power_in"))
      (node (ref "U2") (pin "29_7") (pinfunction "GND_29_7") (pintype "power_in"))
      (node (ref "U2") (pin "29_8") (pinfunction "GND_29_8") (pintype "power_in"))
      (node (ref "U2") (pin "29_9") (pinfunction "GND_29_9") (pintype "power_in"))
      (node (ref "U3") (pin "4") (pinfunction "GND_4") (pintype "power_in"))
      (node (ref "U3") (pin "9") (pinfunction "EXP_9") (pintype "passive"))
      (node (ref "U4") (pin "1") (pinfunction "CTG_1") (pintype "power_in"))
      (node (ref "U4") (pin "4") (pinfunction "GND_4") (pintype "power_in"))
      (node (ref "U4") (pin "6") (pinfunction "QSTRT_6") (pintype "input"))
      (node (ref "U4") (pin "9") (pinfunction "EP_9") (pintype "power_in"))
    )
    (net (code "14") (name "GPIO8") (class "Default")
      (node (ref "R1") (pin "1") (pinfunction "1_1") (pintype "passive"))
      (node (ref "U2") (pin "10") (pinfunction "IO8_10") (pintype "bidirectional"))
    )
    (net (code "15") (name "I2C_PW") (class "Default")
      (node (ref "C1") (pin "1") (pinfunction "1_1") (pintype "passive"))
      (node (ref "C2") (pin "1") (pinfunction "1_1") (pintype "passive"))
      (node (ref "R1_PINH") (pin "2") (pinfunction "2_2") (pintype "passive"))
      (node (ref "R2_PINH") (pin "2") (pinfunction "2_2") (pintype "passive"))
      (node (ref "SENSOR2") (pin "2") (pinfunction "CSB_2") (pintype "input"))
      (node (ref "SENSOR2") (pin "6") (pinfunction "VDDIO_6") (pintype "power_in"))
      (node (ref "SENSOR2") (pin "8") (pinfunction "VDD_8") (pintype "power_in"))
      (node (ref "U2") (pin "17") (pinfunction "IO19_17") (pintype "bidirectional"))
    )
    (net (code "16") (name "INT_RTC") (class "Default")
      (node (ref "R1_PINH1") (pin "1") (pinfunction "1_1") (pintype "passive"))
      (node (ref "TP15") (pin "TP") (pinfunction "TP_TP") (pintype "input"))
      (node (ref "U1") (pin "3") (pinfunction "SQW/~{INT}_3") (pintype "output"))
      (node (ref "U2") (pin "8") (pinfunction "IO0_8") (pintype "bidirectional"))
    )
    (net (code "17") (name "IO{slash}BOOT") (class "Default")
      (node (ref "BOOT_BUTTON") (pin "3") (pinfunction "3_3") (pintype "passive"))
      (node (ref "BOOT_BUTTON") (pin "4") (pinfunction "4_4") (pintype "passive"))
      (node (ref "C6") (pin "1") (pinfunction "1_1") (pintype "passive"))
      (node (ref "R_BOOT") (pin "1") (pinfunction "1_1") (pintype "passive"))
      (node (ref "U2") (pin "15") (pinfunction "IO9_15") (pintype "bidirectional"))
    )
    (net (code "18") (name "IO{slash}CHANGE") (class "Default")
      (node (ref "C10") (pin "1") (pinfunction "1_1") (pintype "passive"))
      (node (ref "CHANGE_BUTTON") (pin "3") (pinfunction "3_3") (pintype "passive"))
      (node (ref "CHANGE_BUTTON") (pin "4") (pinfunction "4_4") (pintype "passive"))
      (node (ref "R_CHANGE") (pin "1") (pinfunction "1_1") (pintype "passive"))
      (node (ref "U2") (pin "23") (pinfunction "IO15_23") (pintype "bidirectional"))
    )
    (net (code "19") (name "MISO") (class "Default")
      (node (ref "D12") (pin "1") (pinfunction "1_1") (pintype "passive"))
      (node (ref "J4") (pin "P7") (pinfunction "DAT0_P7") (pintype "bidirectional"))
      (node (ref "R8") (pin "1") (pinfunction "1_1") (pintype "passive"))
      (node (ref "TP6") (pin "TP") (pinfunction "TP_TP") (pintype "input"))
      (node (ref "U2") (pin "27") (pinfunction "IO2_27") (pintype "bidirectional"))
      (node (ref "U3") (pin "2") (pinfunction "DO(IO1)_2") (pintype "bidirectional"))
    )
    (net (code "20") (name "MOSI") (class "Default")
      (node (ref "D11") (pin "1") (pinfunction "1_1") (pintype "passive"))
      (node (ref "J1") (pin "14") (pinfunction "14_14") (pintype "bidirectional"))
      (node (ref "J4") (pin "P3") (pinfunction "CMD_P3") (pintype "bidirectional"))
      (node (ref "R7") (pin "1") (pinfunction "1_1") (pintype "passive"))
      (node (ref "TP7") (pin "TP") (pinfunction "TP_TP") (pintype "input"))
      (node (ref "U2") (pin "7") (pinfunction "IO7_7") (pintype "bidirectional"))
      (node (ref "U3") (pin "5") (pinfunction "DI(IO0)_5") (pintype "bidirectional"))
    )
    (net (code "21") (name "Net-(CHG_LED-PadC)") (class "Default")
      (node (ref "CHG_LED") (pin "C") (pinfunction "C_C") (pintype "passive"))
      (node (ref "R1_BAT") (pin "1") (pinfunction "1_1") (pintype "passive"))
    )
    (net (code "22") (name "Net-(D2-CATHODE)") (class "Default")
      (node (ref "C1_BAT1") (pin "1") (pinfunction "1_1") (pintype "passive"))
      (node (ref "D2") (pin "1") (pinfunction "CATHODE_1") (pintype "bidirectional"))
      (node (ref "IC4") (pin "1") (pinfunction "VIN_1") (pintype "bidirectional"))
      (node (ref "IC4") (pin "3") (pinfunction "CE_3") (pintype "bidirectional"))
      (node (ref "Q1") (pin "2") (pinfunction "S_2") (pintype "bidirectional"))
    )
    (net (code "23") (name "Net-(D3-A)") (class "Default")
      (node (ref "C4") (pin "1") (pinfunction "1_1") (pintype "passive"))
      (node (ref "D3") (pin "2") (pinfunction "A_2") (pintype "bidirectional"))
      (node (ref "D4") (pin "1") (pinfunction "K_1") (pintype "bidirectional"))
    )
    (net (code "24") (name "Net-(D7-CATHODE)") (class "Default")
      (node (ref "D7") (pin "1") (pinfunction "CATHODE_1") (pintype "bidirectional"))
      (node (ref "R_CAPACITOR") (pin "2") (pinfunction "2_2") (pintype "passive"))
    )
    (net (code "25") (name "Net-(EPD_C1-Pad2)") (class "Default")
      (node (ref "EPD_C1") (pin "2") (pinfunction "2_2") (pintype "passive"))
      (node (ref "J1") (pin "4") (pinfunction "4_4") (pintype "bidirectional"))
    )
    (net (code "26") (name "Net-(EPD_C2-Pad2)") (class "Default")
      (node (ref "EPD_C2") (pin "2") (pinfunction "2_2") (pintype "passive"))
      (node (ref "J1") (pin "5") (pinfunction "5_5") (pintype "bidirectional"))
    )
    (net (code "27") (name "Net-(EPD_C6-Pad2)") (class "Default")
      (node (ref "EPD_C6") (pin "2") (pinfunction "2_2") (pintype "passive"))
      (node (ref "J1") (pin "18") (pinfunction "18_18") (pintype "bidirectional"))
    )
    (net (code "28") (name "Net-(EPD_C7-Pad2)") (class "Default")
      (node (ref "EPD_C7") (pin "2") (pinfunction "2_2") (pintype "passive"))
      (node (ref "J1") (pin "19") (pinfunction "19_19") (pintype "bidirectional"))
    )
    (net (code "29") (name "Net-(EPD_C8-Pad2)") (class "Default")
      (node (ref "EPD_C8") (pin "2") (pinfunction "2_2") (pintype "passive"))
      (node (ref "J1") (pin "20") (pinfunction "20_20") (pintype "bidirectional"))
    )
    (net (code "30") (name "Net-(EPD_C10-Pad2)") (class "Default")
      (node (ref "EPD_C10") (pin "2") (pinfunction "2_2") (pintype "passive"))
      (node (ref "J1") (pin "22") (pinfunction "22_22") (pintype "bidirectional"))
    )
    (net (code "31") (name "Net-(EPD_C12-Pad2)") (class "Default")
      (node (ref "EPD_C12") (pin "2") (pinfunction "2_2") (pintype "passive"))
      (node (ref "J1") (pin "24") (pinfunction "24_24") (pintype "bidirectional"))
    )
    (net (code "32") (name "Net-(IC1-CT)") (class "Default")
      (node (ref "C_DELAY") (pin "1") (pinfunction "1_1") (pintype "passive"))
      (node (ref "IC1") (pin "5") (pinfunction "CT_5") (pintype "bidirectional"))
    )
    (net (code "33") (name "Net-(J2-PadA5)") (class "Default")
      (node (ref "J2") (pin "A5") (pinfunction "A5_A5") (pintype "bidirectional"))
      (node (ref "R2-USB1") (pin "2") (pinfunction "2_2") (pintype "passive"))
    )
    (net (code "34") (name "Net-(J2-PadB5)") (class "Default")
      (node (ref "J2") (pin "B5") (pinfunction "B5_B5") (pintype "bidirectional"))
      (node (ref "R2-USB") (pin "1") (pinfunction "1_1") (pintype "passive"))
    )
    (net (code "35") (name "Net-(MCP73831-PROG)") (class "Default")
      (node (ref "MCP73831") (pin "5") (pinfunction "PROG_5") (pintype "input"))
      (node (ref "R2_BAT") (pin "2") (pinfunction "2_2") (pintype "passive"))
    )
    (net (code "36") (name "Net-(MCP73831-STAT)") (class "Default")
      (node (ref "MCP73831") (pin "1") (pinfunction "STAT_1") (pintype "output"))
      (node (ref "R1_BAT") (pin "2") (pinfunction "2_2") (pintype "passive"))
    )
    (net (code "37") (name "PREVGH") (class "Default")
      (node (ref "D5") (pin "1") (pinfunction "K_1") (pintype "bidirectional"))
      (node (ref "EPD_C9") (pin "2") (pinfunction "2_2") (pintype "passive"))
      (node (ref "J1") (pin "21") (pinfunction "21_21") (pintype "bidirectional"))
    )
    (net (code "38") (name "PREVGL") (class "Default")
      (node (ref "D4") (pin "2") (pinfunction "A_2") (pintype "bidirectional"))
      (node (ref "EPD_C11") (pin "2") (pinfunction "2_2") (pintype "passive"))
      (node (ref "J1") (pin "23") (pinfunction "23_23") (pintype "bidirectional"))
    )
    (net (code "39") (name "RESE") (class "Default")
      (node (ref "J1") (pin "3") (pinfunction "3_3") (pintype "bidirectional"))
      (node (ref "Q3") (pin "2") (pinfunction "S_2") (pintype "bidirectional"))
      (node (ref "R3") (pin "2") (pinfunction "2_2") (pintype "passive"))
    )
    (net (code "40") (name "RESE'") (class "Default")
      (node (ref "R2") (pin "2") (pinfunction "2_2") (pintype "passive"))
      (node (ref "R3") (pin "1") (pinfunction "1_1") (pintype "passive"))
      (node (ref "SJ1") (pin "2") (pinfunction "2_2") (pintype "passive"))
    )
    (net (code "41") (name "RESET") (class "Default")
      (node (ref "C5") (pin "1") (pinfunction "1_1") (pintype "passive"))
      (node (ref "IC1") (pin "1") (pinfunction "VOUT_1") (pintype "bidirectional"))
      (node (ref "RESET_BUTTON") (pin "3") (pinfunction "3_3") (pintype "passive"))
      (node (ref "RESET_BUTTON") (pin "4") (pinfunction "4_4") (pintype "passive"))
      (node (ref "R_RESET") (pin "1") (pinfunction "1_1") (pintype "passive"))
      (node (ref "U2") (pin "3") (pinfunction "EN_3") (pintype "input"))
    )
    (net (code "42") (name "RTC_RST") (class "Default")
      (node (ref "U1") (pin "4") (pinfunction "~{RST}_4") (pintype "input"))
      (node (ref "U2") (pin "16") (pinfunction "IO18_16") (pintype "bidirectional"))
    )
    (net (code "43") (name "RX") (class "Default")
      (node (ref "TP2") (pin "TP") (pinfunction "TP_TP") (pintype "input"))
      (node (ref "U2") (pin "24") (pinfunction "RXD0/GPIO17_24") (pintype "bidirectional"))
    )
    (net (code "44") (name "SCK") (class "Default")
      (node (ref "D10") (pin "1") (pinfunction "1_1") (pintype "passive"))
      (node (ref "J1") (pin "13") (pinfunction "13_13") (pintype "bidirectional"))
      (node (ref "J4") (pin "P5") (pinfunction "CLK_P5") (pintype "bidirectional"))
      (node (ref "R6") (pin "1") (pinfunction "1_1") (pintype "passive"))
      (node (ref "TP8") (pin "TP") (pinfunction "TP_TP") (pintype "input"))
      (node (ref "U2") (pin "6") (pinfunction "IO6_6") (pintype "bidirectional"))
      (node (ref "U3") (pin "6") (pinfunction "CLK_6") (pintype "input"))
    )
    (net (code "45") (name "SCL") (class "Default")
      (node (ref "J3") (pin "4") (pinfunction "4_4") (pintype "passive"))
      (node (ref "R2_PINH") (pin "1") (pinfunction "1_1") (pintype "passive"))
      (node (ref "SENSOR2") (pin "4") (pinfunction "SCK_4") (pintype "input"))
      (node (ref "U1") (pin "16") (pinfunction "SCL_16") (pintype "input"))
      (node (ref "U2") (pin "20") (pinfunction "IO22_20") (pintype "bidirectional"))
      (node (ref "U4") (pin "7") (pinfunction "SCL_7") (pintype "input"))
    )
    (net (code "46") (name "SDA") (class "Default")
      (node (ref "J3") (pin "3") (pinfunction "3_3") (pintype "passive"))
      (node (ref "R1_PINH") (pin "1") (pinfunction "1_1") (pintype "passive"))
      (node (ref "SENSOR2") (pin "3") (pinfunction "SDI_3") (pintype "bidirectional"))
      (node (ref "U1") (pin "15") (pinfunction "SDA_15") (pintype "bidirectional"))
      (node (ref "U2") (pin "19") (pinfunction "IO21_19") (pintype "bidirectional"))
      (node (ref "U4") (pin "8") (pinfunction "SDA_8") (pintype "bidirectional"))
    )
    (net (code "47") (name "SRC") (class "Default")
      (node (ref "C4") (pin "2") (pinfunction "2_2") (pintype "passive"))
      (node (ref "D5") (pin "2") (pinfunction "A_2") (pintype "bidirectional"))
      (node (ref "L1") (pin "1") (pinfunction "1_1") (pintype "passive"))
      (node (ref "Q3") (pin "3") (pinfunction "D_3") (pintype "bidirectional"))
    )
    (net (code "48") (name "SS_SD") (class "Default")
      (node (ref "D8") (pin "1") (pinfunction "1_1") (pintype "passive"))
      (node (ref "J4") (pin "P2") (pinfunction "CD/DAT3_P2") (pintype "bidirectional"))
      (node (ref "R10") (pin "1") (pinfunction "1_1") (pintype "passive"))
      (node (ref "U2") (pin "4") (pinfunction "IO4_4") (pintype "bidirectional"))
    )
    (net (code "49") (name "TX") (class "Default")
      (node (ref "TP1") (pin "TP") (pinfunction "TP_TP") (pintype "input"))
      (node (ref "U2") (pin "25") (pinfunction "TXD0/GPIO16_25") (pintype "bidirectional"))
    )
    (net (code "50") (name "USB_D+") (class "Default")
      (node (ref "D1") (pin "1") (pinfunction "I/O1_1_1") (pintype "bidirectional"))
      (node (ref "U2") (pin "14") (pinfunction "IO13_14") (pintype "bidirectional"))
    )
    (net (code "51") (name "USB_D-") (class "Default")
      (node (ref "D1") (pin "3") (pinfunction "I/O2_1_3") (pintype "bidirectional"))
      (node (ref "U2") (pin "13") (pinfunction "IO12_13") (pintype "bidirectional"))
    )
    (net (code "52") (name "VBAT") (class "Default")
      (node (ref "C2_BAT") (pin "1") (pinfunction "1_1") (pintype "passive"))
      (node (ref "MCP73831") (pin "3") (pinfunction "VBAT_3") (pintype "power_in"))
      (node (ref "Q1") (pin "3") (pinfunction "D_3") (pintype "bidirectional"))
      (node (ref "TP3") (pin "TP") (pinfunction "TP_TP") (pintype "input"))
      (node (ref "U4") (pin "2") (pinfunction "CELL_2") (pintype "power_in"))
      (node (ref "U4") (pin "3") (pinfunction "VDD_3") (pintype "power_in"))
    )
    (net (code "53") (name "VBUS") (class "Default")
      (node (ref "C1_BAT") (pin "1") (pinfunction "1_1") (pintype "passive"))
      (node (ref "C4_USB") (pin "1") (pinfunction "1_1") (pintype "passive"))
      (node (ref "C5_USB") (pin "1") (pinfunction "1_1") (pintype "passive"))
      (node (ref "CHG_LED") (pin "A") (pinfunction "A_A") (pintype "passive"))
      (node (ref "D1") (pin "5") (pinfunction "VBUS_5") (pintype "bidirectional"))
      (node (ref "D2") (pin "2") (pinfunction "ANODE_2") (pintype "bidirectional"))
      (node (ref "MCP73831") (pin "4") (pinfunction "VIN_4") (pintype "power_in"))
      (node (ref "PFMF.050.1") (pin "2") (pinfunction "2_2") (pintype "passive"))
      (node (ref "Q1") (pin "1") (pinfunction "G_1") (pintype "bidirectional"))
      (node (ref "R1_PWRUSB") (pin "2") (pinfunction "2_2") (pintype "passive"))
      (node (ref "TP14") (pin "TP") (pinfunction "TP_TP") (pintype "input"))
    )
    (net (code "54") (name "VRTC") (class "Default")
      (node (ref "C10_SUPERCAP") (pin "2") (pinfunction "2_2") (pintype "passive"))
      (node (ref "C8") (pin "2") (pinfunction "2_2") (pintype "passive"))
      (node (ref "R_CAPACITOR") (pin "1") (pinfunction "1_1") (pintype "passive"))
      (node (ref "U1") (pin "14") (pinfunction "VBAT_14") (pintype "power_in"))
    )
    (net (code "55") (name "VUSB") (class "Default")
      (node (ref "J2") (pin "A4") (pinfunction "A4_A4") (pintype "bidirectional"))
      (node (ref "J2") (pin "A9") (pinfunction "A9_A9") (pintype "bidirectional"))
      (node (ref "J2") (pin "B4") (pinfunction "B4_B4") (pintype "bidirectional"))
      (node (ref "J2") (pin "B9") (pinfunction "B9_B9") (pintype "bidirectional"))
      (node (ref "PFMF.050.1") (pin "1") (pinfunction "1_1") (pintype "passive"))
    )
    (net (code "56") (name "unconnected-(IC1-NC-Pad4)") (class "Default")
      (node (ref "IC1") (pin "4") (pinfunction "NC_4") (pintype "no_connect"))
    )
    (net (code "57") (name "unconnected-(IC4-NC-Pad4)") (class "Default")
      (node (ref "IC4") (pin "4") (pinfunction "NC_4") (pintype "no_connect"))
    )
    (net (code "58") (name "unconnected-(J1-Pad1)") (class "Default")
      (node (ref "J1") (pin "1") (pinfunction "1_1") (pintype "bidirectional"))
    )
    (net (code "59") (name "unconnected-(J1-Pad6)") (class "Default")
      (node (ref "J1") (pin "6") (pinfunction "6_6") (pintype "bidirectional"))
    )
    (net (code "60") (name "unconnected-(J1-Pad7)") (class "Default")
      (node (ref "J1") (pin "7") (pinfunction "7_7") (pintype "bidirectional"))
    )
    (net (code "61") (name "unconnected-(J2-PadA8)") (class "Default")
      (node (ref "J2") (pin "A8") (pinfunction "A8_A8") (pintype "bidirectional"))
    )
    (net (code "62") (name "unconnected-(J2-PadB8)") (class "Default")
      (node (ref "J2") (pin "B8") (pinfunction "B8_B8") (pintype "bidirectional"))
    )
    (net (code "63") (name "unconnected-(J4-DAT1-PadP8)") (class "Default")
      (node (ref "J4") (pin "P8") (pinfunction "DAT1_P8") (pintype "bidirectional"))
    )
    (net (code "64") (name "unconnected-(J4-DAT2-PadP1)") (class "Default")
      (node (ref "J4") (pin "P1") (pinfunction "DAT2_P1") (pintype "bidirectional"))
    )
    (net (code "65") (name "unconnected-(J4-DETECTION_1-PadS1)") (class "Default")
      (node (ref "J4") (pin "S1") (pinfunction "DETECTION_1_S1") (pintype "bidirectional"))
    )
    (net (code "66") (name "unconnected-(J4-DETECTION_2-PadS2)") (class "Default")
      (node (ref "J4") (pin "S2") (pinfunction "DETECTION_2_S2") (pintype "bidirectional"))
    )
    (net (code "67") (name "unconnected-(U2-NC-Pad22)") (class "Default")
      (node (ref "U2") (pin "22") (pinfunction "NC_22") (pintype "no_connect"))
    )
    (net (code "68") (name "unconnected-(U4-~{ALERT}-Pad5)") (class "Default")
      (node (ref "U4") (pin "5") (pinfunction "~{ALERT}_5") (pintype "output"))
    )
  )
)
